# STM32F103ZET6_MinSystem.net
KiCad netlist of a schematic drawn in Altium Designer
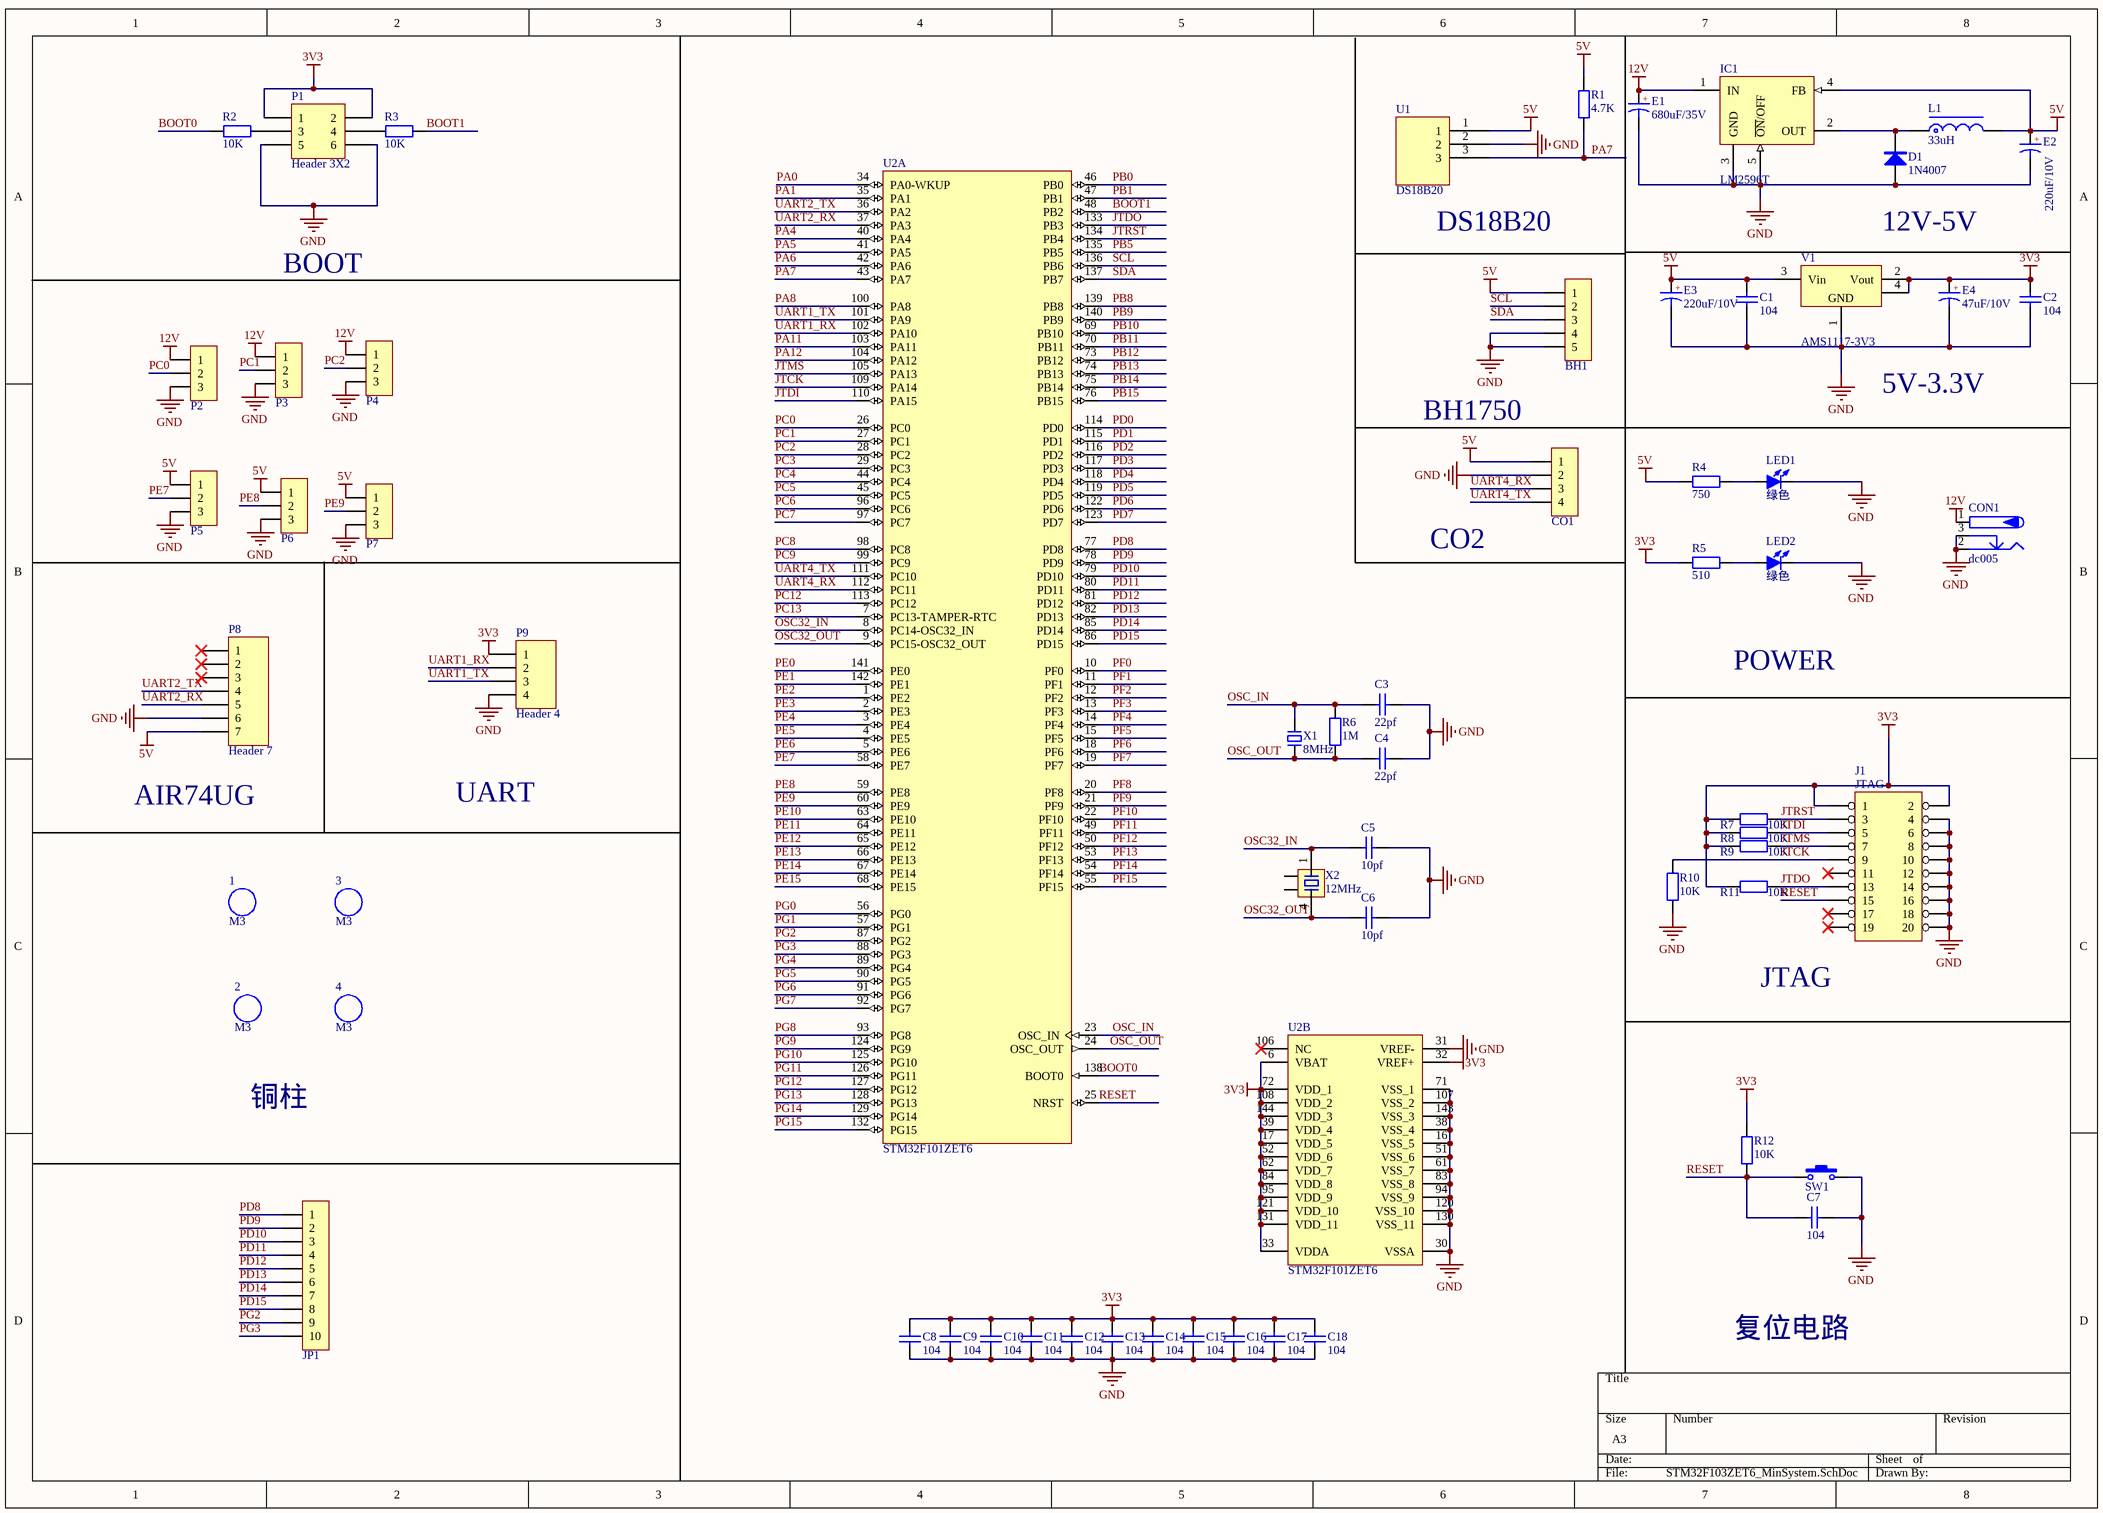
[diagram p0: STM32F103ZET6_MinSystem.SchDoc]

(export (version "E")
  (design (tool "Eeschema 10.0.6"))
  (components
    (comp (ref "1")
      (value "M3")
      (footprint "M3 125X300")
      (description "铜柱孔")
      (libsource (lib "0.5 - 按键_开关_蜂鸣器_保险丝_电池_测试点_Mark点_铜柱") (part "M3"))
    )
    (comp (ref "2")
      (value "M3")
      (footprint "M3 125X300")
      (description "铜柱孔")
      (libsource (lib "0.5 - 按键_开关_蜂鸣器_保险丝_电池_测试点_Mark点_铜柱") (part "M3"))
    )
    (comp (ref "3")
      (value "M3")
      (footprint "M3 125X300")
      (description "铜柱孔")
      (libsource (lib "0.5 - 按键_开关_蜂鸣器_保险丝_电池_测试点_Mark点_铜柱") (part "M3"))
    )
    (comp (ref "4")
      (value "M3")
      (footprint "M3 125X300")
      (description "铜柱孔")
      (libsource (lib "0.5 - 按键_开关_蜂鸣器_保险丝_电池_测试点_Mark点_铜柱") (part "M3"))
    )
    (comp (ref "BH1")
      (value "HDR-1X5")
      (footprint "XH2.54-WI-5P")
      (description "5P接插件")
      (libsource (lib "5.5 - 2.54mm连接器(KF2EDGK_XH2.54_2.54排针排母)") (part "Header 5"))
    )
    (comp (ref "C1")
      (value "104")
      (footprint "C0603_M")
      (description "贴片电容/MLCC电容")
      (libsource (lib "0.1 - 电阻-电容-电感-晶振-晶体-磁珠-电位器-法拉电容-馈通电容") (part "C"))
    )
    (comp (ref "C2")
      (value "104")
      (footprint "C0603_M")
      (description "贴片电容/MLCC电容")
      (libsource (lib "0.1 - 电阻-电容-电感-晶振-晶体-磁珠-电位器-法拉电容-馈通电容") (part "C"))
    )
    (comp (ref "C3")
      (value "22pf")
      (footprint "C0603_M")
      (description "贴片电容/MLCC电容")
      (libsource (lib "0.1 - 电阻-电容-电感-晶振-晶体-磁珠-电位器-法拉电容-馈通电容") (part "C"))
    )
    (comp (ref "C4")
      (value "22pf")
      (footprint "C0603_M")
      (description "贴片电容/MLCC电容")
      (libsource (lib "0.1 - 电阻-电容-电感-晶振-晶体-磁珠-电位器-法拉电容-馈通电容") (part "C"))
    )
    (comp (ref "C5")
      (value "10pf")
      (footprint "C0603_M")
      (description "贴片电容/MLCC电容")
      (libsource (lib "0.1 - 电阻-电容-电感-晶振-晶体-磁珠-电位器-法拉电容-馈通电容") (part "C"))
    )
    (comp (ref "C6")
      (value "10pf")
      (footprint "C0603_M")
      (description "贴片电容/MLCC电容")
      (libsource (lib "0.1 - 电阻-电容-电感-晶振-晶体-磁珠-电位器-法拉电容-馈通电容") (part "C"))
    )
    (comp (ref "C7")
      (value "104")
      (footprint "C0603_M")
      (description "贴片电容/MLCC电容")
      (libsource (lib "0.1 - 电阻-电容-电感-晶振-晶体-磁珠-电位器-法拉电容-馈通电容") (part "C"))
    )
    (comp (ref "C8")
      (value "104")
      (footprint "C0603_M")
      (description "贴片电容/MLCC电容")
      (libsource (lib "0.1 - 电阻-电容-电感-晶振-晶体-磁珠-电位器-法拉电容-馈通电容") (part "C"))
    )
    (comp (ref "C9")
      (value "104")
      (footprint "C0603_M")
      (description "贴片电容/MLCC电容")
      (libsource (lib "0.1 - 电阻-电容-电感-晶振-晶体-磁珠-电位器-法拉电容-馈通电容") (part "C"))
    )
    (comp (ref "C10")
      (value "104")
      (footprint "C0603_M")
      (description "贴片电容/MLCC电容")
      (libsource (lib "0.1 - 电阻-电容-电感-晶振-晶体-磁珠-电位器-法拉电容-馈通电容") (part "C"))
    )
    (comp (ref "C11")
      (value "104")
      (footprint "C0603_M")
      (description "贴片电容/MLCC电容")
      (libsource (lib "0.1 - 电阻-电容-电感-晶振-晶体-磁珠-电位器-法拉电容-馈通电容") (part "C"))
    )
    (comp (ref "C12")
      (value "104")
      (footprint "C0603_M")
      (description "贴片电容/MLCC电容")
      (libsource (lib "0.1 - 电阻-电容-电感-晶振-晶体-磁珠-电位器-法拉电容-馈通电容") (part "C"))
    )
    (comp (ref "C13")
      (value "104")
      (footprint "C0603_M")
      (description "贴片电容/MLCC电容")
      (libsource (lib "0.1 - 电阻-电容-电感-晶振-晶体-磁珠-电位器-法拉电容-馈通电容") (part "C"))
    )
    (comp (ref "C14")
      (value "104")
      (footprint "C0603_M")
      (description "贴片电容/MLCC电容")
      (libsource (lib "0.1 - 电阻-电容-电感-晶振-晶体-磁珠-电位器-法拉电容-馈通电容") (part "C"))
    )
    (comp (ref "C15")
      (value "104")
      (footprint "C0603_M")
      (description "贴片电容/MLCC电容")
      (libsource (lib "0.1 - 电阻-电容-电感-晶振-晶体-磁珠-电位器-法拉电容-馈通电容") (part "C"))
    )
    (comp (ref "C16")
      (value "104")
      (footprint "C0603_M")
      (description "贴片电容/MLCC电容")
      (libsource (lib "0.1 - 电阻-电容-电感-晶振-晶体-磁珠-电位器-法拉电容-馈通电容") (part "C"))
    )
    (comp (ref "C17")
      (value "104")
      (footprint "C0603_M")
      (description "贴片电容/MLCC电容")
      (libsource (lib "0.1 - 电阻-电容-电感-晶振-晶体-磁珠-电位器-法拉电容-馈通电容") (part "C"))
    )
    (comp (ref "C18")
      (value "104")
      (footprint "C0603_M")
      (description "贴片电容/MLCC电容")
      (libsource (lib "0.1 - 电阻-电容-电感-晶振-晶体-磁珠-电位器-法拉电容-馈通电容") (part "C"))
    )
    (comp (ref "CO1")
      (value "HDR-1X4")
      (footprint "XH2.54-WI-4P")
      (description "4P接插件")
      (libsource (lib "5.5 - 2.54mm连接器(KF2EDGK_XH2.54_2.54排针排母)") (part "Header 4"))
    )
    (comp (ref "CON1")
      (value "dc005")
      (footprint "DC-005")
      (description "低压电源接口")
      (libsource (lib "0.6 - 电源_RJ45以太网_音频_SD-TF_SIM_ USB Type-C_HDMI插座") (part "P-DC"))
    )
    (comp (ref "D1")
      (value "1N4007")
      (footprint "SMA")
      (description "整流二极管")
      (libsource (lib "0.2 - 二极管-TVS-ESD-整流桥-放电管") (part "1N4007"))
    )
    (comp (ref "E1")
      (value "680uF/35V")
      (footprint "CE G(12.5*13.5)")
      (description "贴片电解电容")
      (libsource (lib "0.1 - 电阻-电容-电感-晶振-晶体-磁珠-电位器-法拉电容-馈通电容") (part "CE_SMD"))
    )
    (comp (ref "E2")
      (value "220uF/10V")
      (footprint "CE D(6.3*7.7)")
      (description "贴片电解电容")
      (libsource (lib "0.1 - 电阻-电容-电感-晶振-晶体-磁珠-电位器-法拉电容-馈通电容") (part "CE_SMD"))
    )
    (comp (ref "E3")
      (value "220uF/10V")
      (footprint "CE D(6.3*7.7)")
      (description "贴片电解电容")
      (libsource (lib "0.1 - 电阻-电容-电感-晶振-晶体-磁珠-电位器-法拉电容-馈通电容") (part "CE_SMD"))
    )
    (comp (ref "E4")
      (value "47uF/10V")
      (footprint "CE B(4*5.4)")
      (description "贴片电解电容")
      (libsource (lib "0.1 - 电阻-电容-电感-晶振-晶体-磁珠-电位器-法拉电容-馈通电容") (part "CE_SMD"))
    )
    (comp (ref "IC1")
      (value "LM2596T")
      (footprint "TO220-5A")
      (description "3A DC-DC降压芯片")
      (libsource (lib "0.7 - 电源类芯片") (part "LM2596T"))
    )
    (comp (ref "J1") (value "JTAG") (footprint "JTAG_20") (libsource (lib "*") (part "HEADER 10X2")))
    (comp (ref "JP1")
      (value "HDR-1X10")
      (footprint "HDR1.27-LI-10P")
      (description "10P连接器")
      (libsource (lib "5.2 - 1.27mm连接器(1.27排针排母)") (part "Header 10"))
    )
    (comp (ref "L1")
      (value "33uH")
      (footprint "CDRH74")
      (description "CDRH功率屏蔽电感")
      (libsource (lib "0.1 - 电阻-电容-电感-晶振-晶体-磁珠-电位器-法拉电容-馈通电容") (part "L-CDRH"))
    )
    (comp (ref "LED1")
      (value "绿色")
      (footprint "LED0603_G")
      (description "贴片LED")
      (libsource (lib "0.3 - LED发光二极管-IR二极管_接收管-光耦") (part "LED-SMD"))
    )
    (comp (ref "LED2")
      (value "绿色")
      (footprint "LED0603_G")
      (description "贴片LED")
      (libsource (lib "0.3 - LED发光二极管-IR二极管_接收管-光耦") (part "LED-SMD"))
    )
    (comp (ref "P1")
      (value "Header 3X2")
      (footprint "HDR2X3")
      (description "Header, 3-Pin, Dual row")
      (fields (field (name "PUBLISHER") "Altium Limited"))
      (libsource (lib "Miscellaneous Connectors") (part "Header 3X2"))
    )
    (comp (ref "P2")
      (value "HDR-1X3")
      (footprint "KF128-3.81-3P")
      (description "3P接插件")
      (libsource (lib "5.7 - 3.81mm连接器(KF128)") (part "Header 3"))
    )
    (comp (ref "P3")
      (value "HDR-1X3")
      (footprint "KF128-3.81-3P")
      (description "3P接插件")
      (libsource (lib "5.7 - 3.81mm连接器(KF128)") (part "Header 3"))
    )
    (comp (ref "P4")
      (value "HDR-1X3")
      (footprint "KF128-3.81-3P")
      (description "3P接插件")
      (libsource (lib "5.7 - 3.81mm连接器(KF128)") (part "Header 3"))
    )
    (comp (ref "P5")
      (value "HDR-1X3")
      (footprint "KF128-3.81-3P")
      (description "3P接插件")
      (libsource (lib "5.7 - 3.81mm连接器(KF128)") (part "Header 3"))
    )
    (comp (ref "P6")
      (value "HDR-1X3")
      (footprint "KF128-3.81-3P")
      (description "3P接插件")
      (libsource (lib "5.7 - 3.81mm连接器(KF128)") (part "Header 3"))
    )
    (comp (ref "P7")
      (value "HDR-1X3")
      (footprint "KF128-3.81-3P")
      (description "3P接插件")
      (libsource (lib "5.7 - 3.81mm连接器(KF128)") (part "Header 3"))
    )
    (comp (ref "P8")
      (value "Header 7")
      (footprint "HDR1X7")
      (description "Header, 7-Pin")
      (fields (field (name "PUBLISHER") "Altium Limited"))
      (libsource (lib "Miscellaneous Connectors") (part "Header 7"))
    )
    (comp (ref "P9")
      (value "Header 4")
      (footprint "HDR1X4")
      (description "Header, 4-Pin")
      (fields (field (name "PUBLISHER") "Altium Limited"))
      (libsource (lib "Miscellaneous Connectors") (part "Header 4"))
    )
    (comp (ref "R1")
      (value "4.7K")
      (footprint "R0603_L")
      (description "贴片电阻")
      (libsource (lib "0.1 - 电阻-电容-电感-晶振-晶体-磁珠-电位器-法拉电容-馈通电容") (part "R"))
    )
    (comp (ref "R2")
      (value "10K")
      (footprint "R0603_L")
      (description "贴片电阻")
      (libsource (lib "0.1 - 电阻-电容-电感-晶振-晶体-磁珠-电位器-法拉电容-馈通电容") (part "R"))
    )
    (comp (ref "R3")
      (value "10K")
      (footprint "R0603_L")
      (description "贴片电阻")
      (libsource (lib "0.1 - 电阻-电容-电感-晶振-晶体-磁珠-电位器-法拉电容-馈通电容") (part "R"))
    )
    (comp (ref "R4")
      (value "750")
      (footprint "R0603_L")
      (description "贴片电阻")
      (libsource (lib "0.1 - 电阻-电容-电感-晶振-晶体-磁珠-电位器-法拉电容-馈通电容") (part "R"))
    )
    (comp (ref "R5")
      (value "510")
      (footprint "R0603_L")
      (description "贴片电阻")
      (libsource (lib "0.1 - 电阻-电容-电感-晶振-晶体-磁珠-电位器-法拉电容-馈通电容") (part "R"))
    )
    (comp (ref "R6")
      (value "1M")
      (footprint "R0603_L")
      (description "贴片电阻")
      (libsource (lib "0.1 - 电阻-电容-电感-晶振-晶体-磁珠-电位器-法拉电容-馈通电容") (part "R"))
    )
    (comp (ref "R7")
      (value "10K")
      (footprint "R0603_L")
      (description "贴片电阻")
      (libsource (lib "0.1 - 电阻-电容-电感-晶振-晶体-磁珠-电位器-法拉电容-馈通电容") (part "R"))
    )
    (comp (ref "R8")
      (value "10K")
      (footprint "R0603_L")
      (description "贴片电阻")
      (libsource (lib "0.1 - 电阻-电容-电感-晶振-晶体-磁珠-电位器-法拉电容-馈通电容") (part "R"))
    )
    (comp (ref "R9")
      (value "10K")
      (footprint "R0603_L")
      (description "贴片电阻")
      (libsource (lib "0.1 - 电阻-电容-电感-晶振-晶体-磁珠-电位器-法拉电容-馈通电容") (part "R"))
    )
    (comp (ref "R10")
      (value "10K")
      (footprint "R0603_L")
      (description "贴片电阻")
      (libsource (lib "0.1 - 电阻-电容-电感-晶振-晶体-磁珠-电位器-法拉电容-馈通电容") (part "R"))
    )
    (comp (ref "R11")
      (value "10K")
      (footprint "R0603_L")
      (description "贴片电阻")
      (libsource (lib "0.1 - 电阻-电容-电感-晶振-晶体-磁珠-电位器-法拉电容-馈通电容") (part "R"))
    )
    (comp (ref "R12")
      (value "10K")
      (footprint "R0603_L")
      (description "贴片电阻")
      (libsource (lib "0.1 - 电阻-电容-电感-晶振-晶体-磁珠-电位器-法拉电容-馈通电容") (part "R"))
    )
    (comp (ref "SW1")
      (value "3x6x5")
      (footprint "SW SMD-3*6*2.5")
      (description "微动开关")
      (libsource (lib "0.5 - 按键_开关_蜂鸣器_保险丝_电池_测试点_Mark点_铜柱") (part "SW-PB"))
    )
    (comp (ref "U1")
      (value "DS18B20")
      (footprint "XH2.54-WI-3P")
      (libsource (lib "altium-import") (part "root_0_kf128-5.08-3p_"))
    )
    (comp (ref "U2")
      (value "STM32F101ZET6")
      (footprint "LQFP144_N")
      (libsource (lib "2.4 - STM32 F1系列单片机") (part "STM32F101ZET6"))
    )
    (comp (ref "V1")
      (value "AMS1117-3V3")
      (footprint "SOT223_L")
      (description "三端稳压芯片")
      (libsource (lib "0.7 - 电源类芯片") (part "AMS1117"))
    )
    (comp (ref "X1")
      (value "8MHz")
      (footprint "HC-49S")
      (description "2脚无源晶振(谐振器）")
      (libsource (lib "0.1 - 电阻-电容-电感-晶振-晶体-磁珠-电位器-法拉电容-馈通电容") (part "XTAL-2P"))
    )
    (comp (ref "X2")
      (value "12MHz")
      (footprint "MC-306")
      (description "MC系列4脚无源晶振(谐振器）")
      (libsource (lib "0.1 - 电阻-电容-电感-晶振-晶体-磁珠-电位器-法拉电容-馈通电容") (part "XTAL-MC-4P"))
    )
  )
  (nets
    (net (code "1") (name "/BOOT0") (class "Default")
      (node (ref "R2") (pin "1") (pinfunction "1_1") (pintype "passive"))
      (node (ref "U2") (pin "138") (pinfunction "BOOT0_138") (pintype "input"))
    )
    (net (code "2") (name "/BOOT1") (class "Default")
      (node (ref "R3") (pin "1") (pinfunction "1_1") (pintype "passive"))
      (node (ref "U2") (pin "48") (pinfunction "PB2_48") (pintype "bidirectional"))
    )
    (net (code "3") (name "/JTCK") (class "Default")
      (node (ref "J1") (pin "9") (pinfunction "9_9") (pintype "passive"))
      (node (ref "R10") (pin "2") (pinfunction "2_2") (pintype "passive"))
      (node (ref "U2") (pin "109") (pinfunction "PA14_109") (pintype "bidirectional"))
    )
    (net (code "4") (name "/JTDI") (class "Default")
      (node (ref "J1") (pin "5") (pinfunction "5_5") (pintype "passive"))
      (node (ref "R8") (pin "2") (pinfunction "2_2") (pintype "passive"))
      (node (ref "U2") (pin "110") (pinfunction "PA15_110") (pintype "bidirectional"))
    )
    (net (code "5") (name "/JTDO") (class "Default")
      (node (ref "J1") (pin "13") (pinfunction "13_13") (pintype "passive"))
      (node (ref "R11") (pin "2") (pinfunction "2_2") (pintype "passive"))
      (node (ref "U2") (pin "133") (pinfunction "PB3_133") (pintype "bidirectional"))
    )
    (net (code "6") (name "/JTMS") (class "Default")
      (node (ref "J1") (pin "7") (pinfunction "7_7") (pintype "passive"))
      (node (ref "R9") (pin "2") (pinfunction "2_2") (pintype "passive"))
      (node (ref "U2") (pin "105") (pinfunction "PA13_105") (pintype "bidirectional"))
    )
    (net (code "7") (name "/JTRST") (class "Default")
      (node (ref "J1") (pin "3") (pinfunction "3_3") (pintype "passive"))
      (node (ref "R7") (pin "2") (pinfunction "2_2") (pintype "passive"))
      (node (ref "U2") (pin "134") (pinfunction "PB4_134") (pintype "bidirectional"))
    )
    (net (code "8") (name "/OSC32_IN") (class "Default")
      (node (ref "C5") (pin "1") (pinfunction "1_1") (pintype "passive"))
      (node (ref "U2") (pin "8") (pinfunction "PC14-OSC32_IN_8") (pintype "bidirectional"))
      (node (ref "X2") (pin "1") (pinfunction "1_1") (pintype "passive"))
    )
    (net (code "9") (name "/OSC32_OUT") (class "Default")
      (node (ref "C6") (pin "1") (pinfunction "1_1") (pintype "passive"))
      (node (ref "U2") (pin "9") (pinfunction "PC15-OSC32_OUT_9") (pintype "bidirectional"))
      (node (ref "X2") (pin "4") (pinfunction "4_4") (pintype "passive"))
    )
    (net (code "10") (name "/OSC_IN") (class "Default")
      (node (ref "C3") (pin "1") (pinfunction "1_1") (pintype "passive"))
      (node (ref "R6") (pin "2") (pinfunction "2_2") (pintype "passive"))
      (node (ref "U2") (pin "23") (pinfunction "OSC_IN_23") (pintype "input"))
      (node (ref "X1") (pin "1") (pinfunction "1_1") (pintype "passive"))
    )
    (net (code "11") (name "/OSC_OUT") (class "Default")
      (node (ref "C4") (pin "1") (pinfunction "1_1") (pintype "passive"))
      (node (ref "R6") (pin "1") (pinfunction "1_1") (pintype "passive"))
      (node (ref "U2") (pin "24") (pinfunction "OSC_OUT_24") (pintype "output"))
      (node (ref "X1") (pin "2") (pinfunction "2_2") (pintype "passive"))
    )
    (net (code "12") (name "/PA0") (class "Default")
      (node (ref "U2") (pin "34") (pinfunction "PA0-WKUP_34") (pintype "bidirectional"))
    )
    (net (code "13") (name "/PA1") (class "Default")
      (node (ref "U2") (pin "35") (pinfunction "PA1_35") (pintype "bidirectional"))
    )
    (net (code "14") (name "/PA4") (class "Default")
      (node (ref "U2") (pin "40") (pinfunction "PA4_40") (pintype "bidirectional"))
    )
    (net (code "15") (name "/PA5") (class "Default")
      (node (ref "U2") (pin "41") (pinfunction "PA5_41") (pintype "bidirectional"))
    )
    (net (code "16") (name "/PA6") (class "Default")
      (node (ref "U2") (pin "42") (pinfunction "PA6_42") (pintype "bidirectional"))
    )
    (net (code "17") (name "/PA7") (class "Default")
      (node (ref "R1") (pin "1") (pinfunction "1_1") (pintype "passive"))
      (node (ref "U1") (pin "3") (pinfunction "3_3") (pintype "passive"))
      (node (ref "U2") (pin "43") (pinfunction "PA7_43") (pintype "bidirectional"))
    )
    (net (code "18") (name "/PA8") (class "Default")
      (node (ref "U2") (pin "100") (pinfunction "PA8_100") (pintype "bidirectional"))
    )
    (net (code "19") (name "/PA11") (class "Default")
      (node (ref "U2") (pin "103") (pinfunction "PA11_103") (pintype "bidirectional"))
    )
    (net (code "20") (name "/PA12") (class "Default")
      (node (ref "U2") (pin "104") (pinfunction "PA12_104") (pintype "bidirectional"))
    )
    (net (code "21") (name "/PB0") (class "Default")
      (node (ref "U2") (pin "46") (pinfunction "PB0_46") (pintype "bidirectional"))
    )
    (net (code "22") (name "/PB1") (class "Default")
      (node (ref "U2") (pin "47") (pinfunction "PB1_47") (pintype "bidirectional"))
    )
    (net (code "23") (name "/PB5") (class "Default")
      (node (ref "U2") (pin "135") (pinfunction "PB5_135") (pintype "bidirectional"))
    )
    (net (code "24") (name "/PB8") (class "Default")
      (node (ref "U2") (pin "139") (pinfunction "PB8_139") (pintype "bidirectional"))
    )
    (net (code "25") (name "/PB9") (class "Default")
      (node (ref "U2") (pin "140") (pinfunction "PB9_140") (pintype "bidirectional"))
    )
    (net (code "26") (name "/PB10") (class "Default")
      (node (ref "U2") (pin "69") (pinfunction "PB10_69") (pintype "bidirectional"))
    )
    (net (code "27") (name "/PB11") (class "Default")
      (node (ref "U2") (pin "70") (pinfunction "PB11_70") (pintype "bidirectional"))
    )
    (net (code "28") (name "/PB12") (class "Default")
      (node (ref "U2") (pin "73") (pinfunction "PB12_73") (pintype "bidirectional"))
    )
    (net (code "29") (name "/PB13") (class "Default")
      (node (ref "U2") (pin "74") (pinfunction "PB13_74") (pintype "bidirectional"))
    )
    (net (code "30") (name "/PB14") (class "Default")
      (node (ref "U2") (pin "75") (pinfunction "PB14_75") (pintype "bidirectional"))
    )
    (net (code "31") (name "/PB15") (class "Default")
      (node (ref "U2") (pin "76") (pinfunction "PB15_76") (pintype "bidirectional"))
    )
    (net (code "32") (name "/PC0") (class "Default")
      (node (ref "P2") (pin "2") (pinfunction "2_2") (pintype "passive"))
      (node (ref "U2") (pin "26") (pinfunction "PC0_26") (pintype "bidirectional"))
    )
    (net (code "33") (name "/PC1") (class "Default")
      (node (ref "P3") (pin "2") (pinfunction "2_2") (pintype "passive"))
      (node (ref "U2") (pin "27") (pinfunction "PC1_27") (pintype "bidirectional"))
    )
    (net (code "34") (name "/PC2") (class "Default")
      (node (ref "P4") (pin "2") (pinfunction "2_2") (pintype "passive"))
      (node (ref "U2") (pin "28") (pinfunction "PC2_28") (pintype "bidirectional"))
    )
    (net (code "35") (name "/PC3") (class "Default")
      (node (ref "U2") (pin "29") (pinfunction "PC3_29") (pintype "bidirectional"))
    )
    (net (code "36") (name "/PC4") (class "Default")
      (node (ref "U2") (pin "44") (pinfunction "PC4_44") (pintype "bidirectional"))
    )
    (net (code "37") (name "/PC5") (class "Default")
      (node (ref "U2") (pin "45") (pinfunction "PC5_45") (pintype "bidirectional"))
    )
    (net (code "38") (name "/PC6") (class "Default")
      (node (ref "U2") (pin "96") (pinfunction "PC6_96") (pintype "bidirectional"))
    )
    (net (code "39") (name "/PC7") (class "Default")
      (node (ref "U2") (pin "97") (pinfunction "PC7_97") (pintype "bidirectional"))
    )
    (net (code "40") (name "/PC8") (class "Default")
      (node (ref "U2") (pin "98") (pinfunction "PC8_98") (pintype "bidirectional"))
    )
    (net (code "41") (name "/PC9") (class "Default")
      (node (ref "U2") (pin "99") (pinfunction "PC9_99") (pintype "bidirectional"))
    )
    (net (code "42") (name "/PC12") (class "Default")
      (node (ref "U2") (pin "113") (pinfunction "PC12_113") (pintype "bidirectional"))
    )
    (net (code "43") (name "/PC13") (class "Default")
      (node (ref "U2") (pin "7") (pinfunction "PC13-TAMPER-RTC_7") (pintype "bidirectional"))
    )
    (net (code "44") (name "/PD0") (class "Default")
      (node (ref "U2") (pin "114") (pinfunction "PD0_114") (pintype "bidirectional"))
    )
    (net (code "45") (name "/PD1") (class "Default")
      (node (ref "U2") (pin "115") (pinfunction "PD1_115") (pintype "bidirectional"))
    )
    (net (code "46") (name "/PD2") (class "Default")
      (node (ref "U2") (pin "116") (pinfunction "PD2_116") (pintype "bidirectional"))
    )
    (net (code "47") (name "/PD3") (class "Default")
      (node (ref "U2") (pin "117") (pinfunction "PD3_117") (pintype "bidirectional"))
    )
    (net (code "48") (name "/PD4") (class "Default")
      (node (ref "U2") (pin "118") (pinfunction "PD4_118") (pintype "bidirectional"))
    )
    (net (code "49") (name "/PD5") (class "Default")
      (node (ref "U2") (pin "119") (pinfunction "PD5_119") (pintype "bidirectional"))
    )
    (net (code "50") (name "/PD6") (class "Default")
      (node (ref "U2") (pin "122") (pinfunction "PD6_122") (pintype "bidirectional"))
    )
    (net (code "51") (name "/PD7") (class "Default")
      (node (ref "U2") (pin "123") (pinfunction "PD7_123") (pintype "bidirectional"))
    )
    (net (code "52") (name "/PD8") (class "Default")
      (node (ref "JP1") (pin "1") (pinfunction "1_1") (pintype "passive"))
      (node (ref "U2") (pin "77") (pinfunction "PD8_77") (pintype "bidirectional"))
    )
    (net (code "53") (name "/PD9") (class "Default")
      (node (ref "JP1") (pin "2") (pinfunction "2_2") (pintype "passive"))
      (node (ref "U2") (pin "78") (pinfunction "PD9_78") (pintype "bidirectional"))
    )
    (net (code "54") (name "/PD10") (class "Default")
      (node (ref "JP1") (pin "3") (pinfunction "3_3") (pintype "passive"))
      (node (ref "U2") (pin "79") (pinfunction "PD10_79") (pintype "bidirectional"))
    )
    (net (code "55") (name "/PD11") (class "Default")
      (node (ref "JP1") (pin "4") (pinfunction "4_4") (pintype "passive"))
      (node (ref "U2") (pin "80") (pinfunction "PD11_80") (pintype "bidirectional"))
    )
    (net (code "56") (name "/PD12") (class "Default")
      (node (ref "JP1") (pin "5") (pinfunction "5_5") (pintype "passive"))
      (node (ref "U2") (pin "81") (pinfunction "PD12_81") (pintype "bidirectional"))
    )
    (net (code "57") (name "/PD13") (class "Default")
      (node (ref "JP1") (pin "6") (pinfunction "6_6") (pintype "passive"))
      (node (ref "U2") (pin "82") (pinfunction "PD13_82") (pintype "bidirectional"))
    )
    (net (code "58") (name "/PD14") (class "Default")
      (node (ref "JP1") (pin "7") (pinfunction "7_7") (pintype "passive"))
      (node (ref "U2") (pin "85") (pinfunction "PD14_85") (pintype "bidirectional"))
    )
    (net (code "59") (name "/PD15") (class "Default")
      (node (ref "JP1") (pin "8") (pinfunction "8_8") (pintype "passive"))
      (node (ref "U2") (pin "86") (pinfunction "PD15_86") (pintype "bidirectional"))
    )
    (net (code "60") (name "/PE0") (class "Default")
      (node (ref "U2") (pin "141") (pinfunction "PE0_141") (pintype "bidirectional"))
    )
    (net (code "61") (name "/PE1") (class "Default")
      (node (ref "U2") (pin "142") (pinfunction "PE1_142") (pintype "bidirectional"))
    )
    (net (code "62") (name "/PE2") (class "Default")
      (node (ref "U2") (pin "1") (pinfunction "PE2_1") (pintype "bidirectional"))
    )
    (net (code "63") (name "/PE3") (class "Default")
      (node (ref "U2") (pin "2") (pinfunction "PE3_2") (pintype "bidirectional"))
    )
    (net (code "64") (name "/PE4") (class "Default")
      (node (ref "U2") (pin "3") (pinfunction "PE4_3") (pintype "bidirectional"))
    )
    (net (code "65") (name "/PE5") (class "Default")
      (node (ref "U2") (pin "4") (pinfunction "PE5_4") (pintype "bidirectional"))
    )
    (net (code "66") (name "/PE6") (class "Default")
      (node (ref "U2") (pin "5") (pinfunction "PE6_5") (pintype "bidirectional"))
    )
    (net (code "67") (name "/PE7") (class "Default")
      (node (ref "P5") (pin "2") (pinfunction "2_2") (pintype "passive"))
      (node (ref "U2") (pin "58") (pinfunction "PE7_58") (pintype "bidirectional"))
    )
    (net (code "68") (name "/PE8") (class "Default")
      (node (ref "P6") (pin "2") (pinfunction "2_2") (pintype "passive"))
      (node (ref "U2") (pin "59") (pinfunction "PE8_59") (pintype "bidirectional"))
    )
    (net (code "69") (name "/PE9") (class "Default")
      (node (ref "P7") (pin "2") (pinfunction "2_2") (pintype "passive"))
      (node (ref "U2") (pin "60") (pinfunction "PE9_60") (pintype "bidirectional"))
    )
    (net (code "70") (name "/PE10") (class "Default")
      (node (ref "U2") (pin "63") (pinfunction "PE10_63") (pintype "bidirectional"))
    )
    (net (code "71") (name "/PE11") (class "Default")
      (node (ref "U2") (pin "64") (pinfunction "PE11_64") (pintype "bidirectional"))
    )
    (net (code "72") (name "/PE12") (class "Default")
      (node (ref "U2") (pin "65") (pinfunction "PE12_65") (pintype "bidirectional"))
    )
    (net (code "73") (name "/PE13") (class "Default")
      (node (ref "U2") (pin "66") (pinfunction "PE13_66") (pintype "bidirectional"))
    )
    (net (code "74") (name "/PE14") (class "Default")
      (node (ref "U2") (pin "67") (pinfunction "PE14_67") (pintype "bidirectional"))
    )
    (net (code "75") (name "/PE15") (class "Default")
      (node (ref "U2") (pin "68") (pinfunction "PE15_68") (pintype "bidirectional"))
    )
    (net (code "76") (name "/PF0") (class "Default")
      (node (ref "U2") (pin "10") (pinfunction "PF0_10") (pintype "bidirectional"))
    )
    (net (code "77") (name "/PF1") (class "Default")
      (node (ref "U2") (pin "11") (pinfunction "PF1_11") (pintype "bidirectional"))
    )
    (net (code "78") (name "/PF2") (class "Default")
      (node (ref "U2") (pin "12") (pinfunction "PF2_12") (pintype "bidirectional"))
    )
    (net (code "79") (name "/PF3") (class "Default")
      (node (ref "U2") (pin "13") (pinfunction "PF3_13") (pintype "bidirectional"))
    )
    (net (code "80") (name "/PF4") (class "Default")
      (node (ref "U2") (pin "14") (pinfunction "PF4_14") (pintype "bidirectional"))
    )
    (net (code "81") (name "/PF5") (class "Default")
      (node (ref "U2") (pin "15") (pinfunction "PF5_15") (pintype "bidirectional"))
    )
    (net (code "82") (name "/PF6") (class "Default")
      (node (ref "U2") (pin "18") (pinfunction "PF6_18") (pintype "bidirectional"))
    )
    (net (code "83") (name "/PF7") (class "Default")
      (node (ref "U2") (pin "19") (pinfunction "PF7_19") (pintype "bidirectional"))
    )
    (net (code "84") (name "/PF8") (class "Default")
      (node (ref "U2") (pin "20") (pinfunction "PF8_20") (pintype "bidirectional"))
    )
    (net (code "85") (name "/PF9") (class "Default")
      (node (ref "U2") (pin "21") (pinfunction "PF9_21") (pintype "bidirectional"))
    )
    (net (code "86") (name "/PF10") (class "Default")
      (node (ref "U2") (pin "22") (pinfunction "PF10_22") (pintype "bidirectional"))
    )
    (net (code "87") (name "/PF11") (class "Default")
      (node (ref "U2") (pin "49") (pinfunction "PF11_49") (pintype "bidirectional"))
    )
    (net (code "88") (name "/PF12") (class "Default")
      (node (ref "U2") (pin "50") (pinfunction "PF12_50") (pintype "bidirectional"))
    )
    (net (code "89") (name "/PF13") (class "Default")
      (node (ref "U2") (pin "53") (pinfunction "PF13_53") (pintype "bidirectional"))
    )
    (net (code "90") (name "/PF14") (class "Default")
      (node (ref "U2") (pin "54") (pinfunction "PF14_54") (pintype "bidirectional"))
    )
    (net (code "91") (name "/PF15") (class "Default")
      (node (ref "U2") (pin "55") (pinfunction "PF15_55") (pintype "bidirectional"))
    )
    (net (code "92") (name "/PG0") (class "Default")
      (node (ref "U2") (pin "56") (pinfunction "PG0_56") (pintype "bidirectional"))
    )
    (net (code "93") (name "/PG1") (class "Default")
      (node (ref "U2") (pin "57") (pinfunction "PG1_57") (pintype "bidirectional"))
    )
    (net (code "94") (name "/PG2") (class "Default")
      (node (ref "JP1") (pin "9") (pinfunction "9_9") (pintype "passive"))
      (node (ref "U2") (pin "87") (pinfunction "PG2_87") (pintype "bidirectional"))
    )
    (net (code "95") (name "/PG3") (class "Default")
      (node (ref "JP1") (pin "10") (pinfunction "10_10") (pintype "passive"))
      (node (ref "U2") (pin "88") (pinfunction "PG3_88") (pintype "bidirectional"))
    )
    (net (code "96") (name "/PG4") (class "Default")
      (node (ref "U2") (pin "89") (pinfunction "PG4_89") (pintype "bidirectional"))
    )
    (net (code "97") (name "/PG5") (class "Default")
      (node (ref "U2") (pin "90") (pinfunction "PG5_90") (pintype "bidirectional"))
    )
    (net (code "98") (name "/PG6") (class "Default")
      (node (ref "U2") (pin "91") (pinfunction "PG6_91") (pintype "bidirectional"))
    )
    (net (code "99") (name "/PG7") (class "Default")
      (node (ref "U2") (pin "92") (pinfunction "PG7_92") (pintype "bidirectional"))
    )
    (net (code "100") (name "/PG8") (class "Default")
      (node (ref "U2") (pin "93") (pinfunction "PG8_93") (pintype "bidirectional"))
    )
    (net (code "101") (name "/PG9") (class "Default")
      (node (ref "U2") (pin "124") (pinfunction "PG9_124") (pintype "bidirectional"))
    )
    (net (code "102") (name "/PG10") (class "Default")
      (node (ref "U2") (pin "125") (pinfunction "PG10_125") (pintype "bidirectional"))
    )
    (net (code "103") (name "/PG11") (class "Default")
      (node (ref "U2") (pin "126") (pinfunction "PG11_126") (pintype "bidirectional"))
    )
    (net (code "104") (name "/PG12") (class "Default")
      (node (ref "U2") (pin "127") (pinfunction "PG12_127") (pintype "bidirectional"))
    )
    (net (code "105") (name "/PG13") (class "Default")
      (node (ref "U2") (pin "128") (pinfunction "PG13_128") (pintype "bidirectional"))
    )
    (net (code "106") (name "/PG14") (class "Default")
      (node (ref "U2") (pin "129") (pinfunction "PG14_129") (pintype "bidirectional"))
    )
    (net (code "107") (name "/PG15") (class "Default")
      (node (ref "U2") (pin "132") (pinfunction "PG15_132") (pintype "bidirectional"))
    )
    (net (code "108") (name "/RESET") (class "Default")
      (node (ref "C7") (pin "1") (pinfunction "1_1") (pintype "passive"))
      (node (ref "J1") (pin "15") (pinfunction "15_15") (pintype "passive"))
      (node (ref "R12") (pin "1") (pinfunction "1_1") (pintype "passive"))
      (node (ref "SW1") (pin "1") (pinfunction "1_1") (pintype "passive"))
      (node (ref "U2") (pin "25") (pinfunction "NRST_25") (pintype "bidirectional"))
    )
    (net (code "109") (name "/SCL") (class "Default")
      (node (ref "BH1") (pin "2") (pinfunction "2_2") (pintype "passive"))
      (node (ref "U2") (pin "136") (pinfunction "PB6_136") (pintype "bidirectional"))
    )
    (net (code "110") (name "/SDA") (class "Default")
      (node (ref "BH1") (pin "3") (pinfunction "3_3") (pintype "passive"))
      (node (ref "U2") (pin "137") (pinfunction "PB7_137") (pintype "bidirectional"))
    )
    (net (code "111") (name "/UART1_RX") (class "Default")
      (node (ref "P9") (pin "2") (pinfunction "2_2") (pintype "passive"))
      (node (ref "U2") (pin "102") (pinfunction "PA10_102") (pintype "bidirectional"))
    )
    (net (code "112") (name "/UART1_TX") (class "Default")
      (node (ref "P9") (pin "3") (pinfunction "3_3") (pintype "passive"))
      (node (ref "U2") (pin "101") (pinfunction "PA9_101") (pintype "bidirectional"))
    )
    (net (code "113") (name "/UART2_RX") (class "Default")
      (node (ref "P8") (pin "5") (pinfunction "5_5") (pintype "passive"))
      (node (ref "U2") (pin "37") (pinfunction "PA3_37") (pintype "bidirectional"))
    )
    (net (code "114") (name "/UART2_TX") (class "Default")
      (node (ref "P8") (pin "4") (pinfunction "4_4") (pintype "passive"))
      (node (ref "U2") (pin "36") (pinfunction "PA2_36") (pintype "bidirectional"))
    )
    (net (code "115") (name "/UART4_RX") (class "Default")
      (node (ref "CO1") (pin "3") (pinfunction "3_3") (pintype "passive"))
      (node (ref "U2") (pin "112") (pinfunction "PC11_112") (pintype "bidirectional"))
    )
    (net (code "116") (name "/UART4_TX") (class "Default")
      (node (ref "CO1") (pin "4") (pinfunction "4_4") (pintype "passive"))
      (node (ref "U2") (pin "111") (pinfunction "PC10_111") (pintype "bidirectional"))
    )
    (net (code "117") (name "3V3") (class "Default")
      (node (ref "C10") (pin "2") (pinfunction "2_2") (pintype "passive"))
      (node (ref "C11") (pin "2") (pinfunction "2_2") (pintype "passive"))
      (node (ref "C12") (pin "2") (pinfunction "2_2") (pintype "passive"))
      (node (ref "C13") (pin "2") (pinfunction "2_2") (pintype "passive"))
      (node (ref "C14") (pin "2") (pinfunction "2_2") (pintype "passive"))
      (node (ref "C15") (pin "2") (pinfunction "2_2") (pintype "passive"))
      (node (ref "C16") (pin "2") (pinfunction "2_2") (pintype "passive"))
      (node (ref "C17") (pin "2") (pinfunction "2_2") (pintype "passive"))
      (node (ref "C18") (pin "2") (pinfunction "2_2") (pintype "passive"))
      (node (ref "C2") (pin "2") (pinfunction "2_2") (pintype "passive"))
      (node (ref "C8") (pin "2") (pinfunction "2_2") (pintype "passive"))
      (node (ref "C9") (pin "2") (pinfunction "2_2") (pintype "passive"))
      (node (ref "E4") (pin "1") (pinfunction "1_1") (pintype "passive"))
      (node (ref "J1") (pin "1") (pinfunction "1_1") (pintype "passive"))
      (node (ref "J1") (pin "2") (pinfunction "2_2") (pintype "passive"))
      (node (ref "P1") (pin "1") (pinfunction "1_1") (pintype "passive"))
      (node (ref "P1") (pin "2") (pinfunction "2_2") (pintype "passive"))
      (node (ref "P9") (pin "1") (pinfunction "1_1") (pintype "passive"))
      (node (ref "R11") (pin "1") (pinfunction "1_1") (pintype "passive"))
      (node (ref "R12") (pin "2") (pinfunction "2_2") (pintype "passive"))
      (node (ref "R5") (pin "1") (pinfunction "1_1") (pintype "passive"))
      (node (ref "R7") (pin "1") (pinfunction "1_1") (pintype "passive"))
      (node (ref "R8") (pin "1") (pinfunction "1_1") (pintype "passive"))
      (node (ref "R9") (pin "1") (pinfunction "1_1") (pintype "passive"))
      (node (ref "U2") (pin "108") (pinfunction "VDD_2_108") (pintype "power_in"))
      (node (ref "U2") (pin "121") (pinfunction "VDD_10_121") (pintype "power_in"))
      (node (ref "U2") (pin "131") (pinfunction "VDD_11_131") (pintype "power_in"))
      (node (ref "U2") (pin "144") (pinfunction "VDD_3_144") (pintype "power_in"))
      (node (ref "U2") (pin "17") (pinfunction "VDD_5_17") (pintype "power_in"))
      (node (ref "U2") (pin "32") (pinfunction "VREF+_32") (pintype "power_in"))
      (node (ref "U2") (pin "33") (pinfunction "VDDA_33") (pintype "power_in"))
      (node (ref "U2") (pin "39") (pinfunction "VDD_4_39") (pintype "power_in"))
      (node (ref "U2") (pin "52") (pinfunction "VDD_6_52") (pintype "power_in"))
      (node (ref "U2") (pin "6") (pinfunction "VBAT_6") (pintype "power_in"))
      (node (ref "U2") (pin "62") (pinfunction "VDD_7_62") (pintype "power_in"))
      (node (ref "U2") (pin "72") (pinfunction "VDD_1_72") (pintype "power_in"))
      (node (ref "U2") (pin "84") (pinfunction "VDD_8_84") (pintype "power_in"))
      (node (ref "U2") (pin "95") (pinfunction "VDD_9_95") (pintype "power_in"))
      (node (ref "V1") (pin "2") (pinfunction "Vout_2") (pintype "passive"))
      (node (ref "V1") (pin "4") (pinfunction "GND_4") (pintype "passive"))
    )
    (net (code "118") (name "5V") (class "Default")
      (node (ref "BH1") (pin "1") (pinfunction "1_1") (pintype "passive"))
      (node (ref "C1") (pin "2") (pinfunction "2_2") (pintype "passive"))
      (node (ref "CO1") (pin "1") (pinfunction "1_1") (pintype "passive"))
      (node (ref "E2") (pin "1") (pinfunction "1_1") (pintype "passive"))
      (node (ref "E3") (pin "1") (pinfunction "1_1") (pintype "passive"))
      (node (ref "IC1") (pin "4") (pinfunction "FB_4") (pintype "input"))
      (node (ref "L1") (pin "2") (pinfunction "2_2") (pintype "passive"))
      (node (ref "P5") (pin "1") (pinfunction "1_1") (pintype "passive"))
      (node (ref "P6") (pin "1") (pinfunction "1_1") (pintype "passive"))
      (node (ref "P7") (pin "1") (pinfunction "1_1") (pintype "passive"))
      (node (ref "P8") (pin "7") (pinfunction "7_7") (pintype "passive"))
      (node (ref "R1") (pin "2") (pinfunction "2_2") (pintype "passive"))
      (node (ref "R4") (pin "1") (pinfunction "1_1") (pintype "passive"))
      (node (ref "U1") (pin "1") (pinfunction "1_1") (pintype "passive"))
      (node (ref "V1") (pin "3") (pinfunction "Vin_3") (pintype "passive"))
    )
    (net (code "119") (name "12V") (class "Default")
      (node (ref "CON1") (pin "1") (pintype "power_in"))
      (node (ref "E1") (pin "1") (pinfunction "1_1") (pintype "passive"))
      (node (ref "IC1") (pin "1") (pinfunction "IN_1") (pintype "power_in"))
      (node (ref "P2") (pin "1") (pinfunction "1_1") (pintype "passive"))
      (node (ref "P3") (pin "1") (pinfunction "1_1") (pintype "passive"))
      (node (ref "P4") (pin "1") (pinfunction "1_1") (pintype "passive"))
    )
    (net (code "120") (name "GND") (class "Default")
      (node (ref "BH1") (pin "4") (pinfunction "4_4") (pintype "passive"))
      (node (ref "BH1") (pin "5") (pinfunction "5_5") (pintype "passive"))
      (node (ref "C1") (pin "1") (pinfunction "1_1") (pintype "passive"))
      (node (ref "C10") (pin "1") (pinfunction "1_1") (pintype "passive"))
      (node (ref "C11") (pin "1") (pinfunction "1_1") (pintype "passive"))
      (node (ref "C12") (pin "1") (pinfunction "1_1") (pintype "passive"))
      (node (ref "C13") (pin "1") (pinfunction "1_1") (pintype "passive"))
      (node (ref "C14") (pin "1") (pinfunction "1_1") (pintype "passive"))
      (node (ref "C15") (pin "1") (pinfunction "1_1") (pintype "passive"))
      (node (ref "C16") (pin "1") (pinfunction "1_1") (pintype "passive"))
      (node (ref "C17") (pin "1") (pinfunction "1_1") (pintype "passive"))
      (node (ref "C18") (pin "1") (pinfunction "1_1") (pintype "passive"))
      (node (ref "C2") (pin "1") (pinfunction "1_1") (pintype "passive"))
      (node (ref "C3") (pin "2") (pinfunction "2_2") (pintype "passive"))
      (node (ref "C4") (pin "2") (pinfunction "2_2") (pintype "passive"))
      (node (ref "C5") (pin "2") (pinfunction "2_2") (pintype "passive"))
      (node (ref "C6") (pin "2") (pinfunction "2_2") (pintype "passive"))
      (node (ref "C7") (pin "2") (pinfunction "2_2") (pintype "passive"))
      (node (ref "C8") (pin "1") (pinfunction "1_1") (pintype "passive"))
      (node (ref "C9") (pin "1") (pinfunction "1_1") (pintype "passive"))
      (node (ref "CO1") (pin "2") (pinfunction "2_2") (pintype "passive"))
      (node (ref "CON1") (pin "2") (pintype "power_in"))
      (node (ref "CON1") (pin "3") (pintype "power_in"))
      (node (ref "D1") (pin "1") (pinfunction "A_1") (pintype "passive"))
      (node (ref "E1") (pin "2") (pinfunction "2_2") (pintype "passive"))
      (node (ref "E2") (pin "2") (pinfunction "2_2") (pintype "passive"))
      (node (ref "E3") (pin "2") (pinfunction "2_2") (pintype "passive"))
      (node (ref "E4") (pin "2") (pinfunction "2_2") (pintype "passive"))
      (node (ref "IC1") (pin "3") (pinfunction "GND_3") (pintype "power_in"))
      (node (ref "IC1") (pin "5") (pinfunction "~{ON}/OFF_5") (pintype "input"))
      (node (ref "J1") (pin "10") (pinfunction "10_10") (pintype "passive"))
      (node (ref "J1") (pin "12") (pinfunction "12_12") (pintype "passive"))
      (node (ref "J1") (pin "14") (pinfunction "14_14") (pintype "passive"))
      (node (ref "J1") (pin "16") (pinfunction "16_16") (pintype "passive"))
      (node (ref "J1") (pin "18") (pinfunction "18_18") (pintype "passive"))
      (node (ref "J1") (pin "20") (pinfunction "20_20") (pintype "passive"))
      (node (ref "J1") (pin "4") (pinfunction "4_4") (pintype "passive"))
      (node (ref "J1") (pin "6") (pinfunction "6_6") (pintype "passive"))
      (node (ref "J1") (pin "8") (pinfunction "8_8") (pintype "passive"))
      (node (ref "LED1") (pin "2") (pinfunction "K_2") (pintype "passive"))
      (node (ref "LED2") (pin "2") (pinfunction "K_2") (pintype "passive"))
      (node (ref "P1") (pin "5") (pinfunction "5_5") (pintype "passive"))
      (node (ref "P1") (pin "6") (pinfunction "6_6") (pintype "passive"))
      (node (ref "P2") (pin "3") (pinfunction "3_3") (pintype "passive"))
      (node (ref "P3") (pin "3") (pinfunction "3_3") (pintype "passive"))
      (node (ref "P4") (pin "3") (pinfunction "3_3") (pintype "passive"))
      (node (ref "P5") (pin "3") (pinfunction "3_3") (pintype "passive"))
      (node (ref "P6") (pin "3") (pinfunction "3_3") (pintype "passive"))
      (node (ref "P7") (pin "3") (pinfunction "3_3") (pintype "passive"))
      (node (ref "P8") (pin "6") (pinfunction "6_6") (pintype "passive"))
      (node (ref "P9") (pin "4") (pinfunction "4_4") (pintype "passive"))
      (node (ref "R10") (pin "1") (pinfunction "1_1") (pintype "passive"))
      (node (ref "SW1") (pin "2") (pinfunction "2_2") (pintype "passive"))
      (node (ref "U1") (pin "2") (pinfunction "2_2") (pintype "passive"))
      (node (ref "U2") (pin "107") (pinfunction "VSS_2_107") (pintype "power_in"))
      (node (ref "U2") (pin "120") (pinfunction "VSS_10_120") (pintype "power_in"))
      (node (ref "U2") (pin "130") (pinfunction "VSS_11_130") (pintype "power_in"))
      (node (ref "U2") (pin "143") (pinfunction "VSS_3_143") (pintype "power_in"))
      (node (ref "U2") (pin "16") (pinfunction "VSS_5_16") (pintype "power_in"))
      (node (ref "U2") (pin "30") (pinfunction "VSSA_30") (pintype "power_in"))
      (node (ref "U2") (pin "31") (pinfunction "VREF-_31") (pintype "power_in"))
      (node (ref "U2") (pin "38") (pinfunction "VSS_4_38") (pintype "power_in"))
      (node (ref "U2") (pin "51") (pinfunction "VSS_6_51") (pintype "power_in"))
      (node (ref "U2") (pin "61") (pinfunction "VSS_7_61") (pintype "power_in"))
      (node (ref "U2") (pin "71") (pinfunction "VSS_1_71") (pintype "power_in"))
      (node (ref "U2") (pin "83") (pinfunction "VSS_8_83") (pintype "power_in"))
      (node (ref "U2") (pin "94") (pinfunction "VSS_9_94") (pintype "power_in"))
      (node (ref "V1") (pin "1") (pinfunction "GND_1") (pintype "passive"))
    )
    (net (code "121") (name "Net-(D1-K)") (class "Default")
      (node (ref "D1") (pin "2") (pinfunction "K_2") (pintype "passive"))
      (node (ref "IC1") (pin "2") (pinfunction "OUT_2") (pintype "power_in"))
      (node (ref "L1") (pin "1") (pinfunction "1_1") (pintype "passive"))
    )
    (net (code "122") (name "Net-(LED1-A)") (class "Default")
      (node (ref "LED1") (pin "1") (pinfunction "A_1") (pintype "passive"))
      (node (ref "R4") (pin "2") (pinfunction "2_2") (pintype "passive"))
    )
    (net (code "123") (name "Net-(LED2-A)") (class "Default")
      (node (ref "LED2") (pin "1") (pinfunction "A_1") (pintype "passive"))
      (node (ref "R5") (pin "2") (pinfunction "2_2") (pintype "passive"))
    )
    (net (code "124") (name "Net-(P1-Pad3)") (class "Default")
      (node (ref "P1") (pin "3") (pinfunction "3_3") (pintype "passive"))
      (node (ref "R2") (pin "2") (pinfunction "2_2") (pintype "passive"))
    )
    (net (code "125") (name "Net-(P1-Pad4)") (class "Default")
      (node (ref "P1") (pin "4") (pinfunction "4_4") (pintype "passive"))
      (node (ref "R3") (pin "2") (pinfunction "2_2") (pintype "passive"))
    )
    (net (code "126") (name "unconnected-(J1-Pad11)") (class "Default")
      (node (ref "J1") (pin "11") (pinfunction "11_11") (pintype "passive+no_connect"))
    )
    (net (code "127") (name "unconnected-(J1-Pad17)") (class "Default")
      (node (ref "J1") (pin "17") (pinfunction "17_17") (pintype "passive+no_connect"))
    )
    (net (code "128") (name "unconnected-(J1-Pad19)") (class "Default")
      (node (ref "J1") (pin "19") (pinfunction "19_19") (pintype "passive+no_connect"))
    )
    (net (code "129") (name "unconnected-(P8-Pad1)") (class "Default")
      (node (ref "P8") (pin "1") (pinfunction "1_1") (pintype "passive+no_connect"))
    )
    (net (code "130") (name "unconnected-(P8-Pad2)") (class "Default")
      (node (ref "P8") (pin "2") (pinfunction "2_2") (pintype "passive+no_connect"))
    )
    (net (code "131") (name "unconnected-(P8-Pad3)") (class "Default")
      (node (ref "P8") (pin "3") (pinfunction "3_3") (pintype "passive+no_connect"))
    )
    (net (code "132") (name "unconnected-(U2B-NC-Pad106)") (class "Default")
      (node (ref "U2") (pin "106") (pinfunction "NC_106") (pintype "passive+no_connect"))
    )
    (net (code "133") (name "unconnected-(X2-Pad2)") (class "Default")
      (node (ref "X2") (pin "2") (pinfunction "2_2") (pintype "passive"))
    )
    (net (code "134") (name "unconnected-(X2-Pad3)") (class "Default")
      (node (ref "X2") (pin "3") (pinfunction "3_3") (pintype "passive"))
    )
  )
)
